# USB_to_UART.net
KiCad netlist of a schematic drawn in Altium Designer
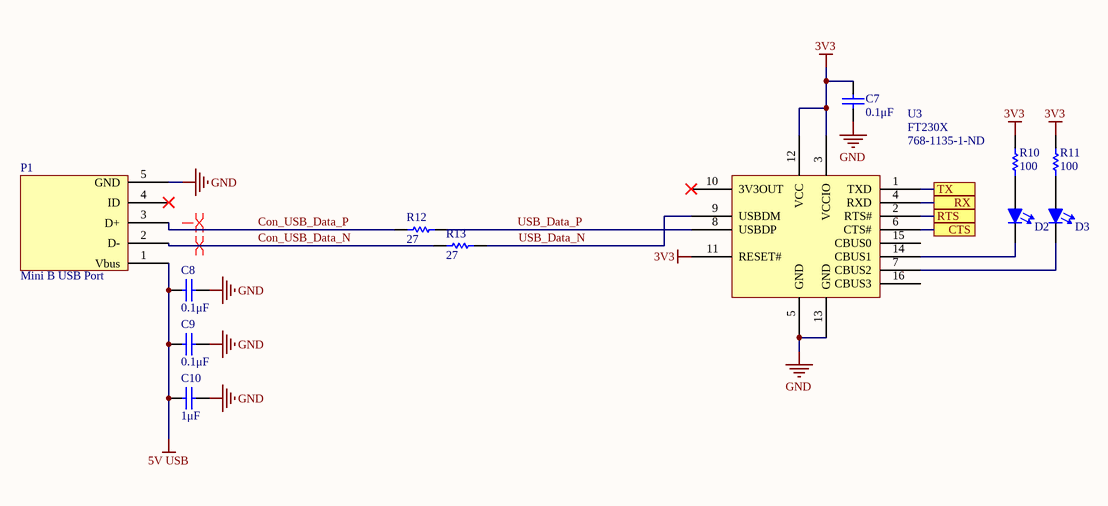
[diagram p0: USB_to_UART.SchDoc]

(export (version "E")
  (design (tool "Eeschema 10.0.6"))
  (components
    (comp (ref "C7")
      (value "0.1μF")
      (footprint "CAPC1608N(0603\")")
      (description "Capacitor, Ceramic, 100V, +/- 10%, 0603 SMD, X7R")
      (fields
        (field (name "MFG") "TDK")
        (field (name "PUBLISHER") "AUVic")
        (field (name "CREATED BY") "Ashwin Sira")
      )
      (libsource (lib "AUVic_Integrated_Library_Capacitors") (part "0.1uF 100V 0603 SMD, Ceramic"))
    )
    (comp (ref "C8")
      (value "0.1μF")
      (footprint "CAPC1608N(0603\")")
      (description "Capacitor, Ceramic, 100V, +/- 10%, 0603 SMD, X7R")
      (fields
        (field (name "MFG") "TDK")
        (field (name "PUBLISHER") "AUVic")
        (field (name "CREATED BY") "Ashwin Sira")
      )
      (libsource (lib "AUVic_Integrated_Library_Capacitors") (part "0.1uF 100V 0603 SMD, Ceramic"))
    )
    (comp (ref "C9")
      (value "0.1μF")
      (footprint "CAPC1608N(0603\")")
      (description "Capacitor, Ceramic, 100V, +/- 10%, 0603 SMD, X7R")
      (fields
        (field (name "MFG") "TDK")
        (field (name "PUBLISHER") "AUVic")
        (field (name "CREATED BY") "Ashwin Sira")
      )
      (libsource (lib "AUVic_Integrated_Library_Capacitors") (part "0.1uF 100V 0603 SMD, Ceramic"))
    )
    (comp (ref "C10")
      (value "1μF")
      (footprint "CAPC1608N(0603\")")
      (description "Capacitor, Ceramic, 25V, +/- 10%, 0603 SMD, X5R")
      (fields
        (field (name "MFG") "Murata-Electronics-North-America")
        (field (name "PUBLISHER") "AUVic")
        (field (name "CREATED BY") "Andy Bates")
      )
      (libsource (lib "AUVic_Integrated_Library_Capacitors") (part "1uF 25V 0603 SMD, Ceramic"))
    )
    (comp (ref "D2")
      (value "Red")
      (footprint "LED0805")
      (description "LED, 0805 (2012), Red, Clear")
      (fields (field (name "CREATED BY") "Ashwin Sira"))
      (libsource (lib "AUVic_Integrated_Library_Diodes") (part "LED, 0805 (2012), Red, Clear"))
    )
    (comp (ref "D3")
      (value "Red")
      (footprint "LED0805")
      (description "LED, 0805 (2012), Red, Clear")
      (fields (field (name "CREATED BY") "Ashwin Sira"))
      (libsource (lib "AUVic_Integrated_Library_Diodes") (part "LED, 0805 (2012), Red, Clear"))
    )
    (comp (ref "P1")
      (value "Mini B USB Port")
      (footprint "Mini B USB Footprint")
      (description "Mini B USB Port - Female")
      (fields (field (name "CREATED BY") "Gabriel Green"))
      (libsource (lib "AUVic_Integrated_Library_Connectors") (part "Mini B USB Port"))
    )
    (comp (ref "R10")
      (value "100")
      (footprint "RESC1608N(0603\")")
      (description "100R, 1%, 1/10W, 0603 SMD")
      (fields (field (name "MADE BY") "Andy Bates"))
      (libsource (lib "AUVic_Integrated_Library_Resistors") (part "100R, 1%, 1/10W, 0603 SMD"))
    )
    (comp (ref "R11")
      (value "100")
      (footprint "RESC1608N(0603\")")
      (description "100R, 1%, 1/10W, 0603 SMD")
      (fields (field (name "MADE BY") "Andy Bates"))
      (libsource (lib "AUVic_Integrated_Library_Resistors") (part "100R, 1%, 1/10W, 0603 SMD"))
    )
    (comp (ref "R12")
      (value "27")
      (footprint "RESC1608N(0603\")")
      (description "27 Ohm, 1%, 1/10W , 0603, SMD")
      (fields (field (name "CREATED BY") "Andy Bates") (field (name "PUBLISHER") "AUVic"))
      (libsource (lib "AUVic_Integrated_Library_Resistors") (part "27 Ohm, 1%, 1/10W , 0603, SMD"))
    )
    (comp (ref "R13")
      (value "27")
      (footprint "RESC1608N(0603\")")
      (description "27 Ohm, 1%, 1/10W , 0603, SMD")
      (fields (field (name "CREATED BY") "Andy Bates") (field (name "PUBLISHER") "AUVic"))
      (libsource (lib "AUVic_Integrated_Library_Resistors") (part "27 Ohm, 1%, 1/10W , 0603, SMD"))
    )
    (comp (ref "U3")
      (value "FT230X")
      (footprint "SSOP16")
      (fields
        (field (name "SUPPLIER PART NUMBER 1") "768-1135-1-ND")
        (field (name "CREATED BY") "Gabriel Green")
      )
      (libsource (lib "AUVic_Integrated_Library_Interface") (part "FTDI - USB to UART"))
    )
  )
  (nets
    (net (code "1") (name "/CTS") (class "Default")
      (node (ref "U3") (pin "6") (pinfunction "CTS#_6") (pintype "passive"))
    )
    (net (code "2") (name "/Con_USB_Data_N") (class "Default")
      (node (ref "P1") (pin "2") (pinfunction "D-_2") (pintype "passive"))
      (node (ref "R13") (pin "2") (pinfunction "2_2") (pintype "passive"))
    )
    (net (code "3") (name "/Con_USB_Data_P") (class "Default")
      (node (ref "P1") (pin "3") (pinfunction "D+_3") (pintype "passive"))
      (node (ref "R12") (pin "2") (pinfunction "2_2") (pintype "passive"))
    )
    (net (code "4") (name "/RTS") (class "Default")
      (node (ref "U3") (pin "2") (pinfunction "RTS#_2") (pintype "passive"))
    )
    (net (code "5") (name "/RX") (class "Default")
      (node (ref "U3") (pin "4") (pinfunction "RXD_4") (pintype "passive"))
    )
    (net (code "6") (name "/TX") (class "Default")
      (node (ref "U3") (pin "1") (pinfunction "TXD_1") (pintype "passive"))
    )
    (net (code "7") (name "/USB_Data_N") (class "Default")
      (node (ref "R13") (pin "1") (pinfunction "1_1") (pintype "passive"))
      (node (ref "U3") (pin "9") (pinfunction "USBDM_9") (pintype "passive"))
    )
    (net (code "8") (name "/USB_Data_P") (class "Default")
      (node (ref "R12") (pin "1") (pinfunction "1_1") (pintype "passive"))
      (node (ref "U3") (pin "8") (pinfunction "USBDP_8") (pintype "passive"))
    )
    (net (code "9") (name "3V3") (class "Default")
      (node (ref "C7") (pin "2") (pinfunction "Cathode_2") (pintype "passive"))
      (node (ref "R10") (pin "2") (pinfunction "2_2") (pintype "passive"))
      (node (ref "R11") (pin "2") (pinfunction "2_2") (pintype "passive"))
      (node (ref "U3") (pin "11") (pinfunction "RESET#_11") (pintype "passive"))
      (node (ref "U3") (pin "12") (pinfunction "VCC_12") (pintype "passive"))
      (node (ref "U3") (pin "3") (pinfunction "VCCIO_3") (pintype "passive"))
    )
    (net (code "10") (name "5V USB") (class "Default")
      (node (ref "C10") (pin "2") (pinfunction "Cathode_2") (pintype "passive"))
      (node (ref "C8") (pin "2") (pinfunction "Cathode_2") (pintype "passive"))
      (node (ref "C9") (pin "2") (pinfunction "Cathode_2") (pintype "passive"))
      (node (ref "P1") (pin "1") (pinfunction "Vbus_1") (pintype "passive"))
    )
    (net (code "11") (name "GND") (class "Default")
      (node (ref "C10") (pin "1") (pinfunction "Anode_1") (pintype "passive"))
      (node (ref "C7") (pin "1") (pinfunction "Anode_1") (pintype "passive"))
      (node (ref "C8") (pin "1") (pinfunction "Anode_1") (pintype "passive"))
      (node (ref "C9") (pin "1") (pinfunction "Anode_1") (pintype "passive"))
      (node (ref "P1") (pin "5") (pinfunction "GND_5") (pintype "passive"))
      (node (ref "U3") (pin "13") (pinfunction "GND_13") (pintype "passive"))
      (node (ref "U3") (pin "5") (pinfunction "GND_5") (pintype "passive"))
    )
    (net (code "12") (name "Net-(D2-Anode)") (class "Default")
      (node (ref "D2") (pin "2") (pinfunction "Anode_2") (pintype "passive"))
      (node (ref "R10") (pin "1") (pinfunction "1_1") (pintype "passive"))
    )
    (net (code "13") (name "Net-(D2-Cathode)") (class "Default")
      (node (ref "D2") (pin "1") (pinfunction "Cathode_1") (pintype "passive"))
      (node (ref "U3") (pin "14") (pinfunction "CBUS1_14") (pintype "passive"))
    )
    (net (code "14") (name "Net-(D3-Anode)") (class "Default")
      (node (ref "D3") (pin "2") (pinfunction "Anode_2") (pintype "passive"))
      (node (ref "R11") (pin "1") (pinfunction "1_1") (pintype "passive"))
    )
    (net (code "15") (name "Net-(D3-Cathode)") (class "Default")
      (node (ref "D3") (pin "1") (pinfunction "Cathode_1") (pintype "passive"))
      (node (ref "U3") (pin "7") (pinfunction "CBUS2_7") (pintype "passive"))
    )
    (net (code "16") (name "unconnected-(P1-ID-Pad4)") (class "Default")
      (node (ref "P1") (pin "4") (pinfunction "ID_4") (pintype "passive+no_connect"))
    )
    (net (code "17") (name "unconnected-(U3-3V3OUT-Pad10)") (class "Default")
      (node (ref "U3") (pin "10") (pinfunction "3V3OUT_10") (pintype "passive+no_connect"))
    )
    (net (code "18") (name "unconnected-(U3-CBUS0-Pad15)") (class "Default")
      (node (ref "U3") (pin "15") (pinfunction "CBUS0_15") (pintype "passive"))
    )
    (net (code "19") (name "unconnected-(U3-CBUS3-Pad16)") (class "Default")
      (node (ref "U3") (pin "16") (pinfunction "CBUS3_16") (pintype "passive"))
    )
  )
)
